# 261105902xxxx-HW-V2_1_20230207.net
KiCad netlist of a schematic drawn in EAGLE
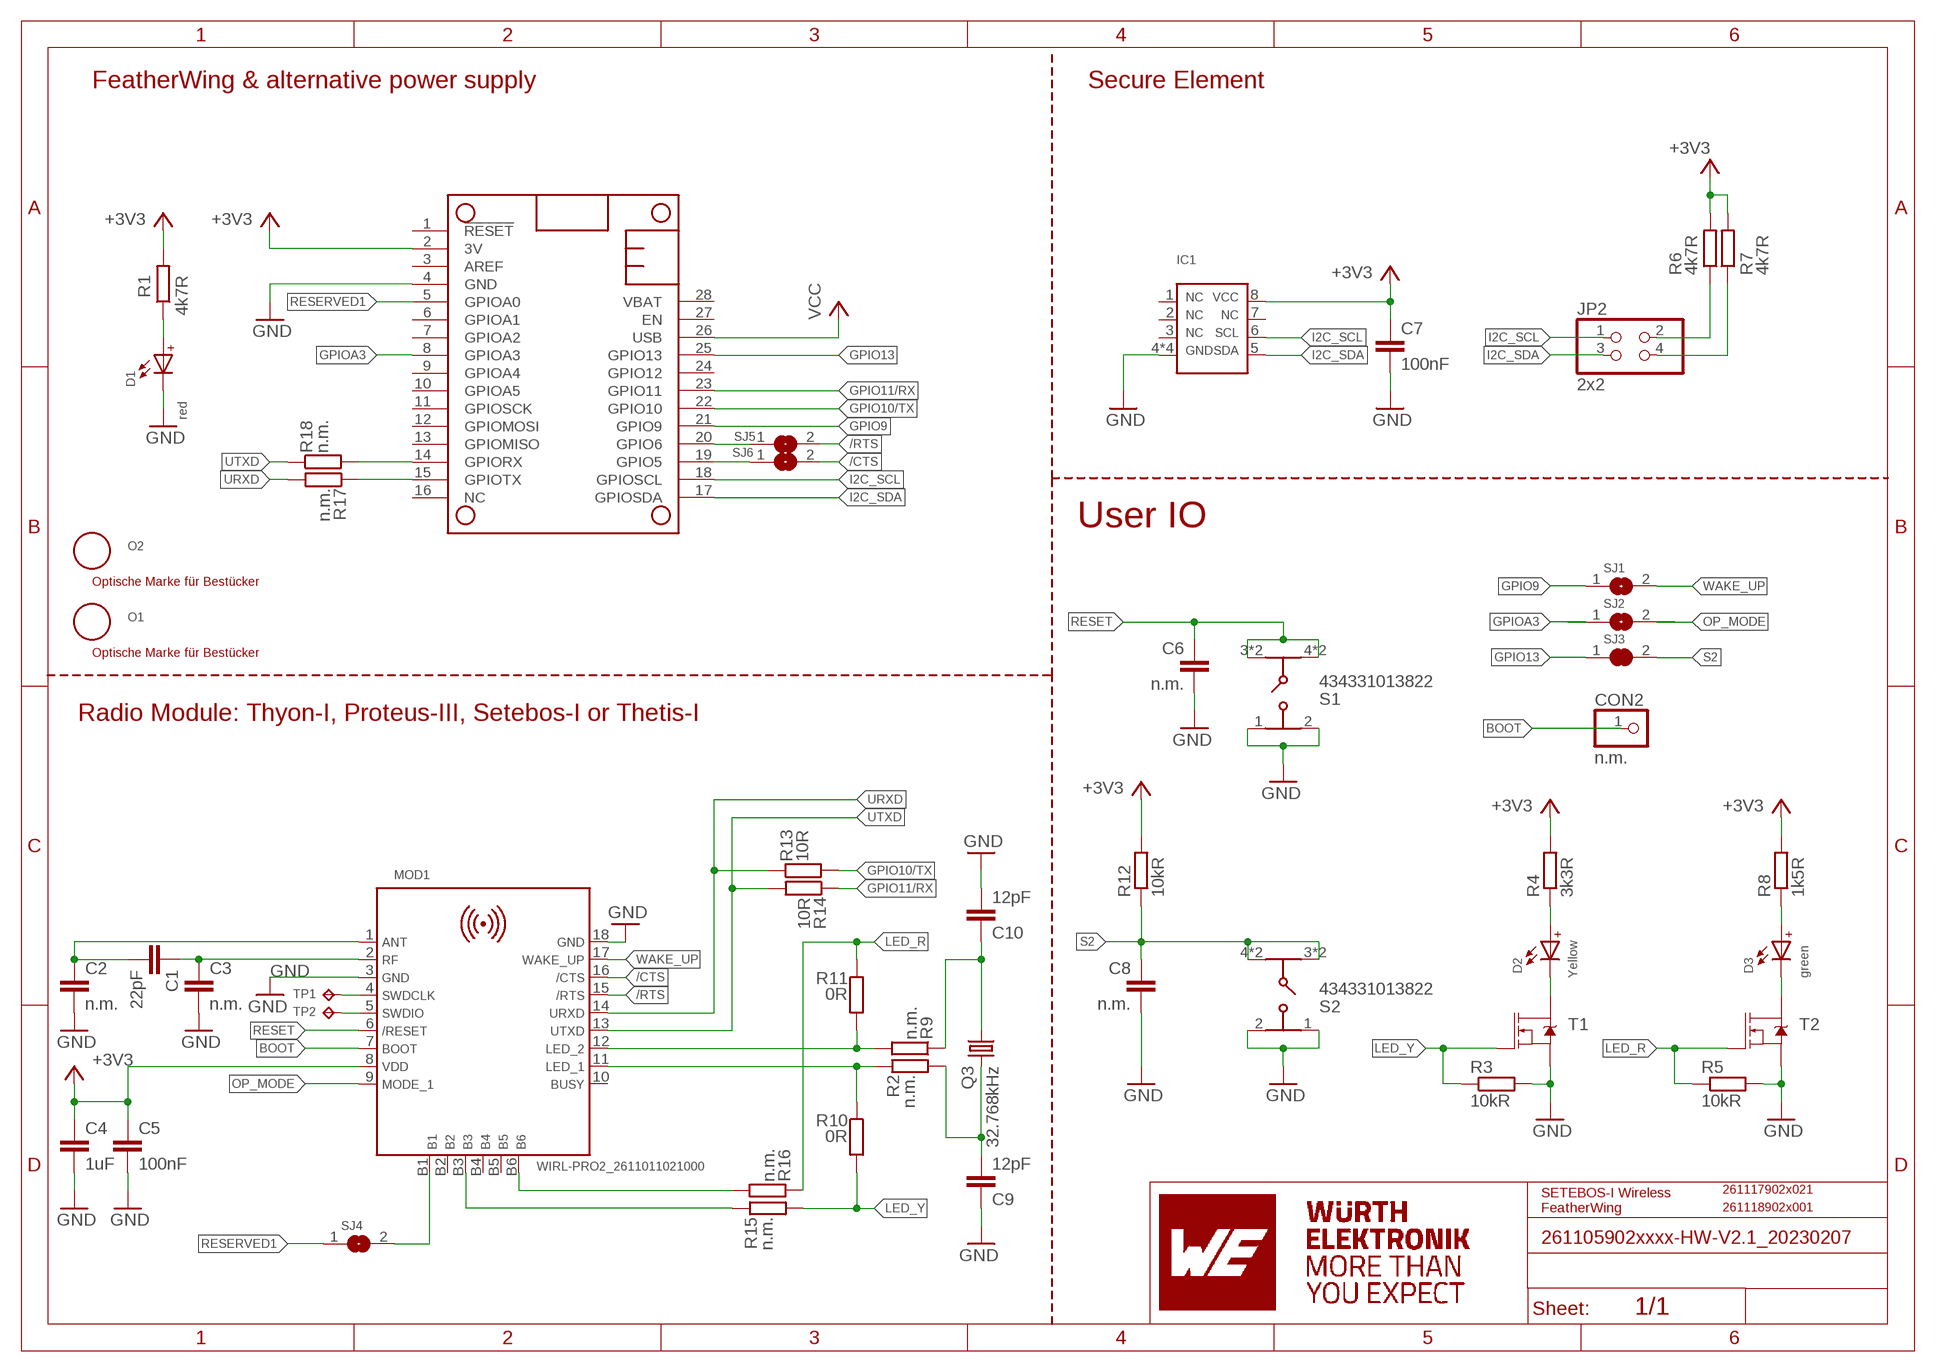
[diagram p0: schematic, sheet 1]

(export (version "E")
  (design (tool "Eeschema 10.0.6"))
  (components
    (comp (ref "C1")
      (value "22pF")
      (footprint "eagle-import:C0402_IPC")
      (fields (field (name "MANUFACTURER") "Würth Elektronik"))
      (libsource (lib "eagle-import") (part "C0402_IPC22PF"))
    )
    (comp (ref "C2")
      (value "n.m.")
      (footprint "eagle-import:C0402_IPC")
      (fields (field (name "MANUFACTURER") "Würth Elektronik"))
      (libsource (lib "eagle-import") (part "C0402_IPC"))
    )
    (comp (ref "C3")
      (value "n.m.")
      (footprint "eagle-import:C0402_IPC")
      (fields (field (name "MANUFACTURER") "Würth Elektronik"))
      (libsource (lib "eagle-import") (part "C0402_IPC"))
    )
    (comp (ref "C4")
      (value "1uF")
      (footprint "eagle-import:C0402_IPC")
      (fields (field (name "MANUFACTURER") "Würth Elektronik"))
      (libsource (lib "eagle-import") (part "C0402_IPC1UF"))
    )
    (comp (ref "C5")
      (value "100nF")
      (footprint "eagle-import:C0402_IPC")
      (fields (field (name "MANUFACTURER") "Würth Elektronik"))
      (libsource (lib "eagle-import") (part "C0402_IPC100NF"))
    )
    (comp (ref "C6")
      (value "n.m.")
      (footprint "eagle-import:C0402_IPC")
      (fields (field (name "MANUFACTURER") "Würth Elektronik"))
      (libsource (lib "eagle-import") (part "C0402_IPC"))
    )
    (comp (ref "C7")
      (value "100nF")
      (footprint "eagle-import:C0402_IPC")
      (fields (field (name "MANUFACTURER") "Würth Elektronik"))
      (libsource (lib "eagle-import") (part "C0402_IPC100NF"))
    )
    (comp (ref "C8")
      (value "n.m.")
      (footprint "eagle-import:C0402_IPC")
      (fields (field (name "MANUFACTURER") "Würth Elektronik"))
      (libsource (lib "eagle-import") (part "C0402_IPC"))
    )
    (comp (ref "C9")
      (value "12pF")
      (footprint "eagle-import:C0402_IPC")
      (fields (field (name "MANUFACTURER") "Yageo"))
      (libsource (lib "eagle-import") (part "C0402_IPC12PF"))
    )
    (comp (ref "C10")
      (value "12pF")
      (footprint "eagle-import:C0402_IPC")
      (fields (field (name "MANUFACTURER") "Yageo"))
      (libsource (lib "eagle-import") (part "C0402_IPC12PF"))
    )
    (comp (ref "CON2")
      (value "n.m.")
      (footprint "eagle-import:1X01_R")
      (libsource (lib "eagle-import") (part "PINHD-1X1/R"))
    )
    (comp (ref "D1")
      (value "red")
      (footprint "eagle-import:WL-SMSW_1204_A")
      (fields (field (name "MANUFACTURER") "Würth Elektronik"))
      (libsource (lib "eagle-import") (part "WL-SMSW_1204_155124VS73200"))
    )
    (comp (ref "D2")
      (value "Yellow")
      (footprint "eagle-import:WL-SMSW_1204_A")
      (fields (field (name "MANUFACTURER") "Würth Elektronik"))
      (libsource (lib "eagle-import") (part "WL-SMSW_1204_155124YS73200"))
    )
    (comp (ref "D3")
      (value "green")
      (footprint "eagle-import:WL-SMSW_1204_A")
      (fields (field (name "MANUFACTURER") "Würth Elektronik"))
      (libsource (lib "eagle-import") (part "WL-SMSW_1204_155124VS73200"))
    )
    (comp (ref "IC1")
      (value "ATECC608B")
      (footprint "eagle-import:UDFN-8")
      (fields (field (name "MANUFACTURER") "Microchip") (field (name "MANUFACTURER_1") "microchip"))
      (libsource (lib "eagle-import") (part "ATECC608B-TNGTLS"))
    )
    (comp (ref "JP2")
      (value "2x2")
      (footprint "eagle-import:2X02")
      (fields (field (name "MANUFACTURER") "Würth Elektronik"))
      (libsource (lib "eagle-import") (part "PINHD-2X2"))
    )
    (comp (ref "MOD1")
      (value "WIRL-PRO2_2611011021000")
      (footprint "eagle-import:WIRL-PRO2_2611011021000")
      (fields (field (name "MANUFACTURER") "Würth Elektronik"))
      (libsource (lib "eagle-import") (part "WIRL-PRO2_2611011021000"))
    )
    (comp (ref "MS1")
      (value "header: 1 x 12 & 1 x 16")
      (footprint "eagle-import:FEATHERWING")
      (fields (field (name "COMMENT") "Kit containing 2 headers") (field (name "MANUFACTURER") "Adafruit"))
      (libsource (lib "eagle-import") (part "FEATHERWING"))
    )
    (comp (ref "O1")
      (value "n.m.")
      (footprint "eagle-import:OPTISCHE_MARKE")
      (libsource (lib "eagle-import") (part "OPT_MARKE"))
    )
    (comp (ref "O2")
      (value "n.m.")
      (footprint "eagle-import:OPTISCHE_MARKE")
      (libsource (lib "eagle-import") (part "OPT_MARKE"))
    )
    (comp (ref "Q3")
      (value "32.768kHz")
      (footprint "eagle-import:3216")
      (fields
        (field (name "MANUFACTURER") "Microcrystal")
        (field (name "MANUFACTURER_1") "Würth Elektronik")
        (field (name "MANUFACTURER_2") "Microcrystal")
        (field (name "NR") "830009706")
        (field (name "NR_2") "CM7V-T1A-32.768k-9pF-20PPM-TA-QA T3")
      )
      (libsource (lib "eagle-import") (part "3216"))
    )
    (comp (ref "R1")
      (value "4k7R")
      (footprint "eagle-import:R0402_IPC")
      (fields (field (name "MANUFACTURER") "Yageo"))
      (libsource (lib "eagle-import") (part "R0402_IPC4K7"))
    )
    (comp (ref "R2")
      (value "n.m.")
      (footprint "eagle-import:R0402_IPC")
      (fields (field (name "MANUFACTURER") "Yageo"))
      (libsource (lib "eagle-import") (part "R0402_IPC"))
    )
    (comp (ref "R3")
      (value "10kR")
      (footprint "eagle-import:R0402_IPC")
      (fields (field (name "MANUFACTURER") "Yageo"))
      (libsource (lib "eagle-import") (part "R0402_IPC10KR"))
    )
    (comp (ref "R4")
      (value "3k3R")
      (footprint "eagle-import:R0402_IPC")
      (fields (field (name "MANUFACTURER") "Yageo"))
      (libsource (lib "eagle-import") (part "R0402_IPC3K3R"))
    )
    (comp (ref "R5")
      (value "10kR")
      (footprint "eagle-import:R0402_IPC")
      (fields (field (name "MANUFACTURER") "Yageo"))
      (libsource (lib "eagle-import") (part "R0402_IPC10KR"))
    )
    (comp (ref "R6")
      (value "4k7R")
      (footprint "eagle-import:R0402_IPC")
      (fields (field (name "MANUFACTURER") "Yageo"))
      (libsource (lib "eagle-import") (part "R0402_IPC4K7"))
    )
    (comp (ref "R7")
      (value "4k7R")
      (footprint "eagle-import:R0402_IPC")
      (fields (field (name "MANUFACTURER") "Yageo"))
      (libsource (lib "eagle-import") (part "R0402_IPC4K7"))
    )
    (comp (ref "R8")
      (value "1k5R")
      (footprint "eagle-import:R0402_IPC")
      (fields (field (name "MANUFACTURER") "Yageo"))
      (libsource (lib "eagle-import") (part "R0402_IPC1K5R"))
    )
    (comp (ref "R9")
      (value "n.m.")
      (footprint "eagle-import:R0402_IPC")
      (fields (field (name "MANUFACTURER") "Yageo"))
      (libsource (lib "eagle-import") (part "R0402_IPC"))
    )
    (comp (ref "R10")
      (value "0R")
      (footprint "eagle-import:R0402_IPC")
      (fields (field (name "MANUFACTURER") "Yageo"))
      (libsource (lib "eagle-import") (part "R0402_IPC0R"))
    )
    (comp (ref "R11")
      (value "0R")
      (footprint "eagle-import:R0402_IPC")
      (fields (field (name "MANUFACTURER") "Yageo"))
      (libsource (lib "eagle-import") (part "R0402_IPC0R"))
    )
    (comp (ref "R12")
      (value "10kR")
      (footprint "eagle-import:R0402_IPC")
      (fields (field (name "MANUFACTURER") "Yageo"))
      (libsource (lib "eagle-import") (part "R0402_IPC10KR"))
    )
    (comp (ref "R13")
      (value "10R")
      (footprint "eagle-import:R0402_IPC")
      (fields (field (name "MANUFACTURER") "Yageo"))
      (libsource (lib "eagle-import") (part "R0402_IPC10R"))
    )
    (comp (ref "R14")
      (value "10R")
      (footprint "eagle-import:R0402_IPC")
      (fields (field (name "MANUFACTURER") "Yageo"))
      (libsource (lib "eagle-import") (part "R0402_IPC10R"))
    )
    (comp (ref "R15")
      (value "n.m.")
      (footprint "eagle-import:R0402_IPC")
      (fields (field (name "MANUFACTURER") "Yageo"))
      (libsource (lib "eagle-import") (part "R0402_IPC"))
    )
    (comp (ref "R16")
      (value "n.m.")
      (footprint "eagle-import:R0402_IPC")
      (fields (field (name "MANUFACTURER") "Yageo"))
      (libsource (lib "eagle-import") (part "R0402_IPC"))
    )
    (comp (ref "R17")
      (value "n.m.")
      (footprint "eagle-import:R0402_IPC")
      (fields (field (name "MANUFACTURER") "Yageo"))
      (libsource (lib "eagle-import") (part "R0402_IPC"))
    )
    (comp (ref "R18")
      (value "n.m.")
      (footprint "eagle-import:R0402_IPC")
      (fields (field (name "MANUFACTURER") "Yageo"))
      (libsource (lib "eagle-import") (part "R0402_IPC"))
    )
    (comp (ref "S1")
      (value "434331013822")
      (footprint "eagle-import:434331013822")
      (fields (field (name "MANUFACTURER") "Würth Elektronik"))
      (libsource (lib "eagle-import") (part "434331013822"))
    )
    (comp (ref "S2")
      (value "434331013822")
      (footprint "eagle-import:434331013822")
      (fields (field (name "MANUFACTURER") "Würth Elektronik"))
      (libsource (lib "eagle-import") (part "434331013822"))
    )
    (comp (ref "SJ1") (value "SJ") (footprint "eagle-import:SJ") (libsource (lib "eagle-import") (part "SJ")))
    (comp (ref "SJ2") (value "SJ") (footprint "eagle-import:SJ") (libsource (lib "eagle-import") (part "SJ")))
    (comp (ref "SJ3")
      (value "SJ_SHUNTD")
      (footprint "eagle-import:SJ_D")
      (libsource (lib "eagle-import") (part "SJ_SHUNTD"))
    )
    (comp (ref "SJ4") (value "SJ") (footprint "eagle-import:SJ") (libsource (lib "eagle-import") (part "SJ")))
    (comp (ref "SJ5") (value "SJ") (footprint "eagle-import:SJ") (libsource (lib "eagle-import") (part "SJ")))
    (comp (ref "SJ6") (value "SJ") (footprint "eagle-import:SJ") (libsource (lib "eagle-import") (part "SJ")))
    (comp (ref "T1")
      (value "MOSFET-NCH-BSS138")
      (footprint "eagle-import:SOT23-3")
      (fields (field (name "COMMENT") "220mA/50V/3.5O") (field (name "MANUFACTURER") "Diodes Incorporated"))
      (libsource (lib "eagle-import") (part "MOSFET-NCH-BSS138"))
    )
    (comp (ref "T2")
      (value "MOSFET-NCH-BSS138")
      (footprint "eagle-import:SOT23-3")
      (fields (field (name "COMMENT") "220mA/50V/3.5O") (field (name "MANUFACTURER") "Diodes Incorporated"))
      (libsource (lib "eagle-import") (part "MOSFET-NCH-BSS138"))
    )
    (comp (ref "TP1")
      (value "TP15R")
      (footprint "eagle-import:TP15R")
      (libsource (lib "eagle-import") (part "TP15R"))
    )
    (comp (ref "TP2")
      (value "TP15R")
      (footprint "eagle-import:TP15R")
      (libsource (lib "eagle-import") (part "TP15R"))
    )
  )
  (nets
    (net (code "1") (name "+3V3") (class "Default")
      (node (ref "C4") (pin "1") (pinfunction "1_1") (pintype "passive"))
      (node (ref "C5") (pin "1") (pinfunction "1_1") (pintype "passive"))
      (node (ref "C7") (pin "1") (pinfunction "1_1") (pintype "passive"))
      (node (ref "IC1") (pin "8") (pinfunction "VCC_8") (pintype "power_in"))
      (node (ref "MOD1") (pin "8") (pinfunction "VDD_8") (pintype "bidirectional"))
      (node (ref "MS1") (pin "2") (pinfunction "3V_2") (pintype "power_in"))
      (node (ref "R1") (pin "2") (pinfunction "2_2") (pintype "passive"))
      (node (ref "R12") (pin "2") (pinfunction "2_2") (pintype "passive"))
      (node (ref "R4") (pin "2") (pinfunction "2_2") (pintype "passive"))
      (node (ref "R6") (pin "2") (pinfunction "2_2") (pintype "passive"))
      (node (ref "R7") (pin "2") (pinfunction "2_2") (pintype "passive"))
      (node (ref "R8") (pin "2") (pinfunction "2_2") (pintype "passive"))
    )
    (net (code "2") (name "/VBAT") (class "Default")
      (node (ref "MS1") (pin "28") (pinfunction "VBAT_28") (pintype "power_in"))
    )
    (net (code "3") (name "BOOT") (class "Default")
      (node (ref "CON2") (pin "1") (pinfunction "1_1") (pintype "passive"))
      (node (ref "MOD1") (pin "7") (pinfunction "P0.02/BOOT_7") (pintype "bidirectional"))
    )
    (net (code "4") (name "GND") (class "Default")
      (node (ref "C10") (pin "2") (pinfunction "2_2") (pintype "passive"))
      (node (ref "C2") (pin "2") (pinfunction "2_2") (pintype "passive"))
      (node (ref "C3") (pin "2") (pinfunction "2_2") (pintype "passive"))
      (node (ref "C4") (pin "2") (pinfunction "2_2") (pintype "passive"))
      (node (ref "C5") (pin "2") (pinfunction "2_2") (pintype "passive"))
      (node (ref "C6") (pin "2") (pinfunction "2_2") (pintype "passive"))
      (node (ref "C7") (pin "2") (pinfunction "2_2") (pintype "passive"))
      (node (ref "C8") (pin "2") (pinfunction "2_2") (pintype "passive"))
      (node (ref "C9") (pin "1") (pinfunction "1_1") (pintype "passive"))
      (node (ref "D1") (pin "1") (pinfunction "-_1") (pintype "passive"))
      (node (ref "IC1") (pin "4") (pinfunction "GND_4") (pintype "power_in"))
      (node (ref "IC1") (pin "P$1") (pinfunction "GND_P$1") (pintype "power_in"))
      (node (ref "IC1") (pin "P$2") (pinfunction "GND_P$2") (pintype "power_in"))
      (node (ref "IC1") (pin "THERMAL_PAD") (pinfunction "GND_THERMAL_PAD") (pintype "power_in"))
      (node (ref "MOD1") (pin "18") (pinfunction "GND_18") (pintype "bidirectional"))
      (node (ref "MOD1") (pin "3") (pinfunction "GND_3") (pintype "bidirectional"))
      (node (ref "MS1") (pin "4") (pinfunction "GND_4") (pintype "power_in"))
      (node (ref "R3") (pin "2") (pinfunction "2_2") (pintype "passive"))
      (node (ref "R5") (pin "2") (pinfunction "2_2") (pintype "passive"))
      (node (ref "S1") (pin "1") (pinfunction "1_1") (pintype "passive"))
      (node (ref "S1") (pin "2") (pinfunction "2_2") (pintype "passive"))
      (node (ref "S2") (pin "1") (pinfunction "1_1") (pintype "passive"))
      (node (ref "S2") (pin "2") (pinfunction "2_2") (pintype "passive"))
      (node (ref "T1") (pin "2") (pinfunction "S_2") (pintype "bidirectional"))
      (node (ref "T2") (pin "2") (pinfunction "S_2") (pintype "bidirectional"))
    )
    (net (code "5") (name "GPIO9") (class "Default")
      (node (ref "MS1") (pin "21") (pinfunction "GPIO9_21") (pintype "bidirectional"))
      (node (ref "SJ1") (pin "1") (pinfunction "1_1") (pintype "passive"))
    )
    (net (code "6") (name "GPIO10{slash}TX") (class "Default")
      (node (ref "MS1") (pin "22") (pinfunction "GPIO10_22") (pintype "bidirectional"))
      (node (ref "R13") (pin "2") (pinfunction "2_2") (pintype "passive"))
    )
    (net (code "7") (name "GPIO11{slash}RX") (class "Default")
      (node (ref "MS1") (pin "23") (pinfunction "GPIO11_23") (pintype "bidirectional"))
      (node (ref "R14") (pin "1") (pinfunction "1_1") (pintype "passive"))
    )
    (net (code "8") (name "GPIO13") (class "Default")
      (node (ref "MS1") (pin "25") (pinfunction "GPIO13_25") (pintype "bidirectional"))
      (node (ref "SJ3") (pin "1") (pinfunction "1_1") (pintype "passive"))
    )
    (net (code "9") (name "GPIOA3") (class "Default")
      (node (ref "MS1") (pin "8") (pinfunction "GPIOA3_8") (pintype "bidirectional"))
      (node (ref "SJ2") (pin "1") (pinfunction "1_1") (pintype "passive"))
    )
    (net (code "10") (name "I2C_SCL") (class "Default")
      (node (ref "IC1") (pin "6") (pinfunction "SCL_6") (pintype "bidirectional"))
      (node (ref "JP2") (pin "1") (pinfunction "1_1") (pintype "passive"))
      (node (ref "MS1") (pin "18") (pinfunction "GPIOSCL_18") (pintype "bidirectional"))
    )
    (net (code "11") (name "I2C_SDA") (class "Default")
      (node (ref "IC1") (pin "5") (pinfunction "SDA_5") (pintype "bidirectional"))
      (node (ref "JP2") (pin "3") (pinfunction "3_3") (pintype "passive"))
      (node (ref "MS1") (pin "17") (pinfunction "GPIOSDA_17") (pintype "bidirectional"))
    )
    (net (code "12") (name "LED_R") (class "Default")
      (node (ref "R11") (pin "1") (pinfunction "1_1") (pintype "passive"))
      (node (ref "R16") (pin "1") (pinfunction "1_1") (pintype "passive"))
      (node (ref "R5") (pin "1") (pinfunction "1_1") (pintype "passive"))
      (node (ref "T2") (pin "1") (pinfunction "G_1") (pintype "bidirectional"))
    )
    (net (code "13") (name "LED_Y") (class "Default")
      (node (ref "R10") (pin "2") (pinfunction "2_2") (pintype "passive"))
      (node (ref "R15") (pin "2") (pinfunction "2_2") (pintype "passive"))
      (node (ref "R3") (pin "1") (pinfunction "1_1") (pintype "passive"))
      (node (ref "T1") (pin "1") (pinfunction "G_1") (pintype "bidirectional"))
    )
    (net (code "14") (name "Net-(C9-Pad2)") (class "Default")
      (node (ref "C9") (pin "2") (pinfunction "2_2") (pintype "passive"))
      (node (ref "Q3") (pin "2") (pinfunction "2_2") (pintype "passive"))
      (node (ref "R2") (pin "2") (pinfunction "2_2") (pintype "passive"))
    )
    (net (code "15") (name "Net-(C10-Pad1)") (class "Default")
      (node (ref "C10") (pin "1") (pinfunction "1_1") (pintype "passive"))
      (node (ref "Q3") (pin "1") (pinfunction "1_1") (pintype "passive"))
      (node (ref "R9") (pin "1") (pinfunction "1_1") (pintype "passive"))
    )
    (net (code "16") (name "Net-(D1-+)") (class "Default")
      (node (ref "D1") (pin "2") (pinfunction "+_2") (pintype "passive"))
      (node (ref "R1") (pin "1") (pinfunction "1_1") (pintype "passive"))
    )
    (net (code "17") (name "Net-(D2-+)") (class "Default")
      (node (ref "D2") (pin "2") (pinfunction "+_2") (pintype "passive"))
      (node (ref "R4") (pin "1") (pinfunction "1_1") (pintype "passive"))
    )
    (net (code "18") (name "Net-(D2--)") (class "Default")
      (node (ref "D2") (pin "1") (pinfunction "-_1") (pintype "passive"))
      (node (ref "T1") (pin "3") (pinfunction "D_3") (pintype "bidirectional"))
    )
    (net (code "19") (name "Net-(D3-+)") (class "Default")
      (node (ref "D3") (pin "2") (pinfunction "+_2") (pintype "passive"))
      (node (ref "R8") (pin "1") (pinfunction "1_1") (pintype "passive"))
    )
    (net (code "20") (name "Net-(D3--)") (class "Default")
      (node (ref "D3") (pin "1") (pinfunction "-_1") (pintype "passive"))
      (node (ref "T2") (pin "3") (pinfunction "D_3") (pintype "bidirectional"))
    )
    (net (code "21") (name "Net-(JP2-Pad2)") (class "Default")
      (node (ref "JP2") (pin "2") (pinfunction "2_2") (pintype "passive"))
      (node (ref "R6") (pin "1") (pinfunction "1_1") (pintype "passive"))
    )
    (net (code "22") (name "Net-(JP2-Pad4)") (class "Default")
      (node (ref "JP2") (pin "4") (pinfunction "4_4") (pintype "passive"))
      (node (ref "R7") (pin "1") (pinfunction "1_1") (pintype "passive"))
    )
    (net (code "23") (name "Net-(MOD1-ANT_PAD)") (class "Default")
      (node (ref "C1") (pin "2") (pinfunction "2_2") (pintype "passive"))
      (node (ref "C2") (pin "1") (pinfunction "1_1") (pintype "passive"))
      (node (ref "MOD1") (pin "1") (pinfunction "ANT_PAD_1") (pintype "bidirectional"))
    )
    (net (code "24") (name "Net-(MOD1-P0.00{slash}LED_1)") (class "Default")
      (node (ref "MOD1") (pin "11") (pinfunction "P0.00/LED_1_11") (pintype "bidirectional"))
      (node (ref "R10") (pin "1") (pinfunction "1_1") (pintype "passive"))
      (node (ref "R2") (pin "1") (pinfunction "1_1") (pintype "passive"))
    )
    (net (code "25") (name "Net-(MOD1-P0.01{slash}LED_2)") (class "Default")
      (node (ref "MOD1") (pin "12") (pinfunction "P0.01/LED_2_12") (pintype "bidirectional"))
      (node (ref "R11") (pin "2") (pinfunction "2_2") (pintype "passive"))
      (node (ref "R9") (pin "2") (pinfunction "2_2") (pintype "passive"))
    )
    (net (code "26") (name "Net-(MOD1-PadB1)") (class "Default")
      (node (ref "MOD1") (pin "B1") (pinfunction "B1_B1") (pintype "bidirectional"))
      (node (ref "SJ4") (pin "2") (pinfunction "2_2") (pintype "passive"))
    )
    (net (code "27") (name "Net-(MOD1-PadB3)") (class "Default")
      (node (ref "MOD1") (pin "B3") (pinfunction "B3_B3") (pintype "bidirectional"))
      (node (ref "R15") (pin "1") (pinfunction "1_1") (pintype "passive"))
    )
    (net (code "28") (name "Net-(MOD1-PadB6)") (class "Default")
      (node (ref "MOD1") (pin "B6") (pinfunction "B6_B6") (pintype "bidirectional"))
      (node (ref "R16") (pin "2") (pinfunction "2_2") (pintype "passive"))
    )
    (net (code "29") (name "Net-(MOD1-RF)") (class "Default")
      (node (ref "C1") (pin "1") (pinfunction "1_1") (pintype "passive"))
      (node (ref "C3") (pin "1") (pinfunction "1_1") (pintype "passive"))
      (node (ref "MOD1") (pin "2") (pinfunction "RF_2") (pintype "bidirectional"))
    )
    (net (code "30") (name "Net-(MOD1-SWDCLK)") (class "Default")
      (node (ref "MOD1") (pin "4") (pinfunction "SWDCLK_4") (pintype "bidirectional"))
      (node (ref "TP1") (pin "P$1") (pinfunction "TP_P$1") (pintype "passive"))
    )
    (net (code "31") (name "Net-(MOD1-SWDIO)") (class "Default")
      (node (ref "MOD1") (pin "5") (pinfunction "SWDIO_5") (pintype "bidirectional"))
      (node (ref "TP2") (pin "P$1") (pinfunction "TP_P$1") (pintype "passive"))
    )
    (net (code "32") (name "Net-(MS1-GPIO5)") (class "Default")
      (node (ref "MS1") (pin "19") (pinfunction "GPIO5_19") (pintype "bidirectional"))
      (node (ref "SJ6") (pin "1") (pinfunction "1_1") (pintype "passive"))
    )
    (net (code "33") (name "Net-(MS1-GPIO6)") (class "Default")
      (node (ref "MS1") (pin "20") (pinfunction "GPIO6_20") (pintype "bidirectional"))
      (node (ref "SJ5") (pin "1") (pinfunction "1_1") (pintype "passive"))
    )
    (net (code "34") (name "Net-(MS1-GPIORX)") (class "Default")
      (node (ref "MS1") (pin "14") (pinfunction "GPIORX_14") (pintype "bidirectional"))
      (node (ref "R18") (pin "2") (pinfunction "2_2") (pintype "passive"))
    )
    (net (code "35") (name "Net-(MS1-GPIOTX)") (class "Default")
      (node (ref "MS1") (pin "15") (pinfunction "GPIOTX_15") (pintype "bidirectional"))
      (node (ref "R17") (pin "1") (pinfunction "1_1") (pintype "passive"))
    )
    (net (code "36") (name "OP_MODE") (class "Default")
      (node (ref "MOD1") (pin "9") (pinfunction "P0.19/MODE_1_9") (pintype "bidirectional"))
      (node (ref "SJ2") (pin "2") (pinfunction "2_2") (pintype "passive"))
    )
    (net (code "37") (name "RESERVED1") (class "Default")
      (node (ref "MS1") (pin "5") (pinfunction "GPIOA0_5") (pintype "bidirectional"))
      (node (ref "SJ4") (pin "1") (pinfunction "1_1") (pintype "passive"))
    )
    (net (code "38") (name "RESET") (class "Default")
      (node (ref "C6") (pin "1") (pinfunction "1_1") (pintype "passive"))
      (node (ref "MOD1") (pin "6") (pinfunction "P0.18/RESET_6") (pintype "bidirectional"))
      (node (ref "S1") (pin "3") (pinfunction "3_3") (pintype "passive"))
      (node (ref "S1") (pin "4") (pinfunction "4_4") (pintype "passive"))
      (node (ref "S1") (pin "5") (pinfunction "3_5") (pintype "passive"))
      (node (ref "S1") (pin "6") (pinfunction "4_6") (pintype "passive"))
    )
    (net (code "39") (name "S2") (class "Default")
      (node (ref "C8") (pin "1") (pinfunction "1_1") (pintype "passive"))
      (node (ref "R12") (pin "1") (pinfunction "1_1") (pintype "passive"))
      (node (ref "S2") (pin "3") (pinfunction "3_3") (pintype "passive"))
      (node (ref "S2") (pin "4") (pinfunction "4_4") (pintype "passive"))
      (node (ref "S2") (pin "5") (pinfunction "3_5") (pintype "passive"))
      (node (ref "S2") (pin "6") (pinfunction "4_6") (pintype "passive"))
      (node (ref "SJ3") (pin "2") (pinfunction "2_2") (pintype "passive"))
    )
    (net (code "40") (name "URXD") (class "Default")
      (node (ref "MOD1") (pin "14") (pinfunction "P1.09/URXD_14") (pintype "bidirectional"))
      (node (ref "R13") (pin "1") (pinfunction "1_1") (pintype "passive"))
      (node (ref "R17") (pin "2") (pinfunction "2_2") (pintype "passive"))
    )
    (net (code "41") (name "UTXD") (class "Default")
      (node (ref "MOD1") (pin "13") (pinfunction "P1.08/UTXD_13") (pintype "bidirectional"))
      (node (ref "R14") (pin "2") (pinfunction "2_2") (pintype "passive"))
      (node (ref "R18") (pin "1") (pinfunction "1_1") (pintype "passive"))
    )
    (net (code "42") (name "VCC") (class "Default")
      (node (ref "MS1") (pin "26") (pinfunction "USB_26") (pintype "power_in"))
    )
    (net (code "43") (name "WAKE_UP") (class "Default")
      (node (ref "MOD1") (pin "17") (pinfunction "P0.03/WAKE_UP_17") (pintype "bidirectional"))
      (node (ref "SJ1") (pin "2") (pinfunction "2_2") (pintype "passive"))
    )
    (net (code "44") (name "unconnected-(IC1-NC1-Pad1)") (class "Default")
      (node (ref "IC1") (pin "1") (pinfunction "NC1_1") (pintype "no_connect"))
    )
    (net (code "45") (name "unconnected-(IC1-NC2-Pad2)") (class "Default")
      (node (ref "IC1") (pin "2") (pinfunction "NC2_2") (pintype "no_connect"))
    )
    (net (code "46") (name "unconnected-(IC1-NC3-Pad3)") (class "Default")
      (node (ref "IC1") (pin "3") (pinfunction "NC3_3") (pintype "no_connect"))
    )
    (net (code "47") (name "unconnected-(IC1-NC4-Pad7)") (class "Default")
      (node (ref "IC1") (pin "7") (pinfunction "NC4_7") (pintype "no_connect"))
    )
    (net (code "48") (name "unconnected-(MOD1-P0.22{slash}BUSY-Pad10)") (class "Default")
      (node (ref "MOD1") (pin "10") (pinfunction "P0.22/BUSY_10") (pintype "bidirectional"))
    )
    (net (code "49") (name "unconnected-(MOD1-PadB2)") (class "Default")
      (node (ref "MOD1") (pin "B2") (pinfunction "B2_B2") (pintype "bidirectional"))
    )
    (net (code "50") (name "unconnected-(MOD1-PadB4)") (class "Default")
      (node (ref "MOD1") (pin "B4") (pinfunction "B4_B4") (pintype "bidirectional"))
    )
    (net (code "51") (name "unconnected-(MOD1-PadB5)") (class "Default")
      (node (ref "MOD1") (pin "B5") (pinfunction "B5_B5") (pintype "bidirectional"))
    )
    (net (code "52") (name "unconnected-(MS1-AREF-Pad3)") (class "Default")
      (node (ref "MS1") (pin "3") (pinfunction "AREF_3") (pintype "passive"))
    )
    (net (code "53") (name "unconnected-(MS1-EN-Pad27)") (class "Default")
      (node (ref "MS1") (pin "27") (pinfunction "EN_27") (pintype "passive"))
    )
    (net (code "54") (name "unconnected-(MS1-GPIO12-Pad24)") (class "Default")
      (node (ref "MS1") (pin "24") (pinfunction "GPIO12_24") (pintype "bidirectional"))
    )
    (net (code "55") (name "unconnected-(MS1-GPIOA1-Pad6)") (class "Default")
      (node (ref "MS1") (pin "6") (pinfunction "GPIOA1_6") (pintype "bidirectional"))
    )
    (net (code "56") (name "unconnected-(MS1-GPIOA2-Pad7)") (class "Default")
      (node (ref "MS1") (pin "7") (pinfunction "GPIOA2_7") (pintype "bidirectional"))
    )
    (net (code "57") (name "unconnected-(MS1-GPIOA4-Pad9)") (class "Default")
      (node (ref "MS1") (pin "9") (pinfunction "GPIOA4_9") (pintype "bidirectional"))
    )
    (net (code "58") (name "unconnected-(MS1-GPIOA5-Pad10)") (class "Default")
      (node (ref "MS1") (pin "10") (pinfunction "GPIOA5_10") (pintype "bidirectional"))
    )
    (net (code "59") (name "unconnected-(MS1-GPIOMISO-Pad13)") (class "Default")
      (node (ref "MS1") (pin "13") (pinfunction "GPIOMISO_13") (pintype "bidirectional"))
    )
    (net (code "60") (name "unconnected-(MS1-GPIOMOSI-Pad12)") (class "Default")
      (node (ref "MS1") (pin "12") (pinfunction "GPIOMOSI_12") (pintype "bidirectional"))
    )
    (net (code "61") (name "unconnected-(MS1-GPIOSCK-Pad11)") (class "Default")
      (node (ref "MS1") (pin "11") (pinfunction "GPIOSCK_11") (pintype "bidirectional"))
    )
    (net (code "62") (name "unconnected-(MS1-NC-Pad16)") (class "Default")
      (node (ref "MS1") (pin "16") (pinfunction "NC_16") (pintype "passive"))
    )
    (net (code "63") (name "unconnected-(MS1-~{RESET}-Pad1)") (class "Default")
      (node (ref "MS1") (pin "1") (pinfunction "~{RESET}_1") (pintype "input"))
    )
    (net (code "64") (name "{slash}CTS") (class "Default")
      (node (ref "MOD1") (pin "16") (pinfunction "P0.12/~{CTS}_16") (pintype "bidirectional"))
      (node (ref "SJ6") (pin "2") (pinfunction "2_2") (pintype "passive"))
    )
    (net (code "65") (name "{slash}RTS") (class "Default")
      (node (ref "MOD1") (pin "15") (pinfunction "P0.11/~{RTS}_15") (pintype "bidirectional"))
      (node (ref "SJ5") (pin "2") (pinfunction "2_2") (pintype "passive"))
    )
  )
)
